# thermal.net
KiCad netlist of a schematic drawn in EAGLE
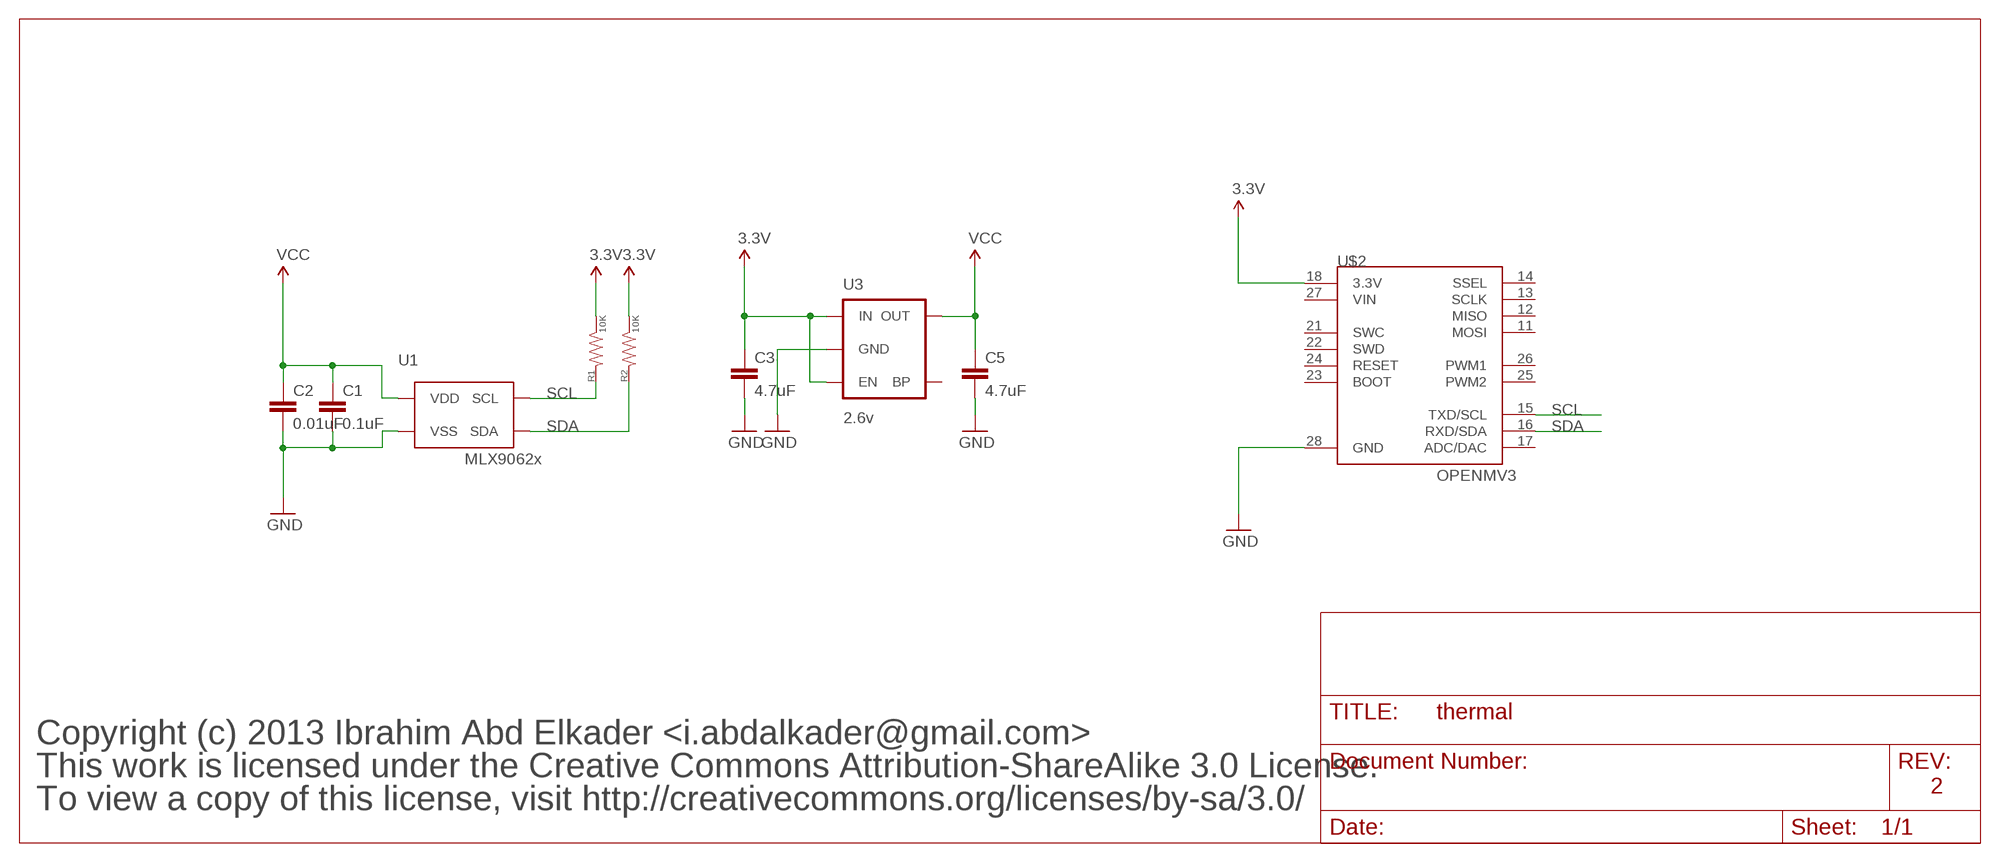
[diagram p0: schematic, sheet 1]

(export (version "E")
  (design (tool "Eeschema 10.0.6"))
  (components
    (comp (ref "C1")
      (value "0.1uF")
      (footprint "eagle-import:0603-CAP")
      (libsource (lib "eagle-import") (part "CAP0603-CAP"))
    )
    (comp (ref "C2")
      (value "0.01uF")
      (footprint "eagle-import:0603-CAP")
      (libsource (lib "eagle-import") (part "CAP0603-CAP"))
    )
    (comp (ref "C3")
      (value "4.7uF")
      (footprint "eagle-import:0603-CAP")
      (libsource (lib "eagle-import") (part "CAP0603-CAP"))
    )
    (comp (ref "C5")
      (value "4.7uF")
      (footprint "eagle-import:0603-CAP")
      (libsource (lib "eagle-import") (part "CAP0603-CAP"))
    )
    (comp (ref "R1")
      (value "10K")
      (footprint "eagle-import:0603-RES")
      (libsource (lib "eagle-import") (part "RESISTOR0603-RES"))
    )
    (comp (ref "R2")
      (value "10K")
      (footprint "eagle-import:0603-RES")
      (libsource (lib "eagle-import") (part "RESISTOR0603-RES"))
    )
    (comp (ref "U$2")
      (value "OPENMV3")
      (footprint "eagle-import:OPENMV3")
      (libsource (lib "eagle-import") (part "OPENMV3"))
    )
    (comp (ref "U1")
      (value "MLX9062x")
      (footprint "eagle-import:TO39_4")
      (libsource (lib "eagle-import") (part "MLX90620"))
    )
    (comp (ref "U3")
      (value "2.6v")
      (footprint "eagle-import:SOT23-5")
      (libsource (lib "eagle-import") (part "V_REG_LDOSMD"))
    )
  )
  (nets
    (net (code "1") (name "/SCL") (class "Default")
      (node (ref "R1") (pin "2") (pinfunction "2_2") (pintype "passive"))
      (node (ref "U$2") (pin "15") (pinfunction "TXD/SCL_15") (pintype "bidirectional"))
      (node (ref "U1") (pin "1") (pinfunction "SCL_1") (pintype "bidirectional"))
    )
    (net (code "2") (name "/SDA") (class "Default")
      (node (ref "R2") (pin "2") (pinfunction "2_2") (pintype "passive"))
      (node (ref "U$2") (pin "16") (pinfunction "RXD/SDA_16") (pintype "bidirectional"))
      (node (ref "U1") (pin "2") (pinfunction "SDA_2") (pintype "bidirectional"))
    )
    (net (code "3") (name "/VIN") (class "Default")
      (node (ref "U$2") (pin "27") (pinfunction "VIN_27") (pintype "power_in"))
    )
    (net (code "4") (name "3.3V") (class "Default")
      (node (ref "C3") (pin "1") (pinfunction "1_1") (pintype "passive"))
      (node (ref "R1") (pin "1") (pinfunction "1_1") (pintype "passive"))
      (node (ref "R2") (pin "1") (pinfunction "1_1") (pintype "passive"))
      (node (ref "U$2") (pin "18") (pinfunction "3.3V_18") (pintype "power_in"))
      (node (ref "U3") (pin "1") (pinfunction "IN_1") (pintype "input"))
      (node (ref "U3") (pin "3") (pinfunction "EN_3") (pintype "input"))
    )
    (net (code "5") (name "GND") (class "Default")
      (node (ref "C1") (pin "2") (pinfunction "2_2") (pintype "passive"))
      (node (ref "C2") (pin "2") (pinfunction "2_2") (pintype "passive"))
      (node (ref "C3") (pin "2") (pinfunction "2_2") (pintype "passive"))
      (node (ref "C5") (pin "2") (pinfunction "2_2") (pintype "passive"))
      (node (ref "U$2") (pin "28") (pinfunction "GND_28") (pintype "power_in"))
      (node (ref "U1") (pin "4") (pinfunction "VSS_4") (pintype "power_in"))
      (node (ref "U3") (pin "2") (pinfunction "GND_2") (pintype "input"))
    )
    (net (code "6") (name "VCC") (class "Default")
      (node (ref "C1") (pin "1") (pinfunction "1_1") (pintype "passive"))
      (node (ref "C2") (pin "1") (pinfunction "1_1") (pintype "passive"))
      (node (ref "C5") (pin "1") (pinfunction "1_1") (pintype "passive"))
      (node (ref "U1") (pin "3") (pinfunction "VDD_3") (pintype "power_in"))
      (node (ref "U3") (pin "5") (pinfunction "OUT_5") (pintype "passive"))
    )
    (net (code "7") (name "unconnected-(U$2-ADC{slash}DAC-Pad17)") (class "Default")
      (node (ref "U$2") (pin "17") (pinfunction "ADC/DAC_17") (pintype "bidirectional"))
    )
    (net (code "8") (name "unconnected-(U$2-BOOT-Pad23)") (class "Default")
      (node (ref "U$2") (pin "23") (pinfunction "BOOT_23") (pintype "bidirectional"))
    )
    (net (code "9") (name "unconnected-(U$2-MISO-Pad12)") (class "Default")
      (node (ref "U$2") (pin "12") (pinfunction "MISO_12") (pintype "bidirectional"))
    )
    (net (code "10") (name "unconnected-(U$2-MOSI-Pad11)") (class "Default")
      (node (ref "U$2") (pin "11") (pinfunction "MOSI_11") (pintype "bidirectional"))
    )
    (net (code "11") (name "unconnected-(U$2-PWM1-Pad26)") (class "Default")
      (node (ref "U$2") (pin "26") (pinfunction "PWM1_26") (pintype "bidirectional"))
    )
    (net (code "12") (name "unconnected-(U$2-PWM2-Pad25)") (class "Default")
      (node (ref "U$2") (pin "25") (pinfunction "PWM2_25") (pintype "bidirectional"))
    )
    (net (code "13") (name "unconnected-(U$2-RESET-Pad24)") (class "Default")
      (node (ref "U$2") (pin "24") (pinfunction "RESET_24") (pintype "bidirectional"))
    )
    (net (code "14") (name "unconnected-(U$2-SCLK-Pad13)") (class "Default")
      (node (ref "U$2") (pin "13") (pinfunction "SCLK_13") (pintype "bidirectional"))
    )
    (net (code "15") (name "unconnected-(U$2-SSEL-Pad14)") (class "Default")
      (node (ref "U$2") (pin "14") (pinfunction "SSEL_14") (pintype "bidirectional"))
    )
    (net (code "16") (name "unconnected-(U$2-SWC-Pad21)") (class "Default")
      (node (ref "U$2") (pin "21") (pinfunction "SWC_21") (pintype "bidirectional"))
    )
    (net (code "17") (name "unconnected-(U$2-SWD-Pad22)") (class "Default")
      (node (ref "U$2") (pin "22") (pinfunction "SWD_22") (pintype "bidirectional"))
    )
    (net (code "18") (name "unconnected-(U3-BP-Pad4)") (class "Default")
      (node (ref "U3") (pin "4") (pinfunction "BP_4") (pintype "input"))
    )
  )
)
